# Sheet.net
KiCad netlist of a schematic drawn in Altium Designer
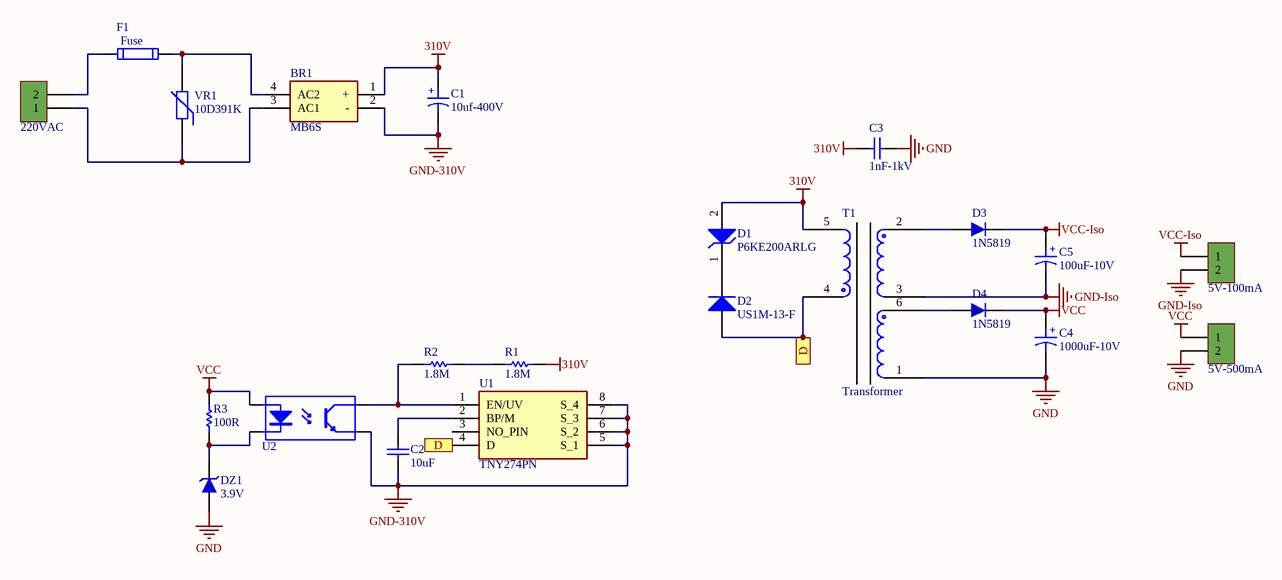
[diagram p0: Sheet.SchDoc]

(export (version "E")
  (design (tool "Eeschema 10.0.6"))
  (components
    (comp (ref "5V-100mA")
      (value "Phoenix 2 Pin")
      (footprint "Phoenix_2PIN_RA_P5.08mm")
      (libsource (lib "Connector") (part "Phoenix 2 Pin"))
    )
    (comp (ref "5V-500mA")
      (value "Phoenix 2 Pin")
      (footprint "Phoenix_2PIN_RA_P5.08mm")
      (libsource (lib "Connector") (part "Phoenix 2 Pin"))
    )
    (comp (ref "220VAC")
      (value "Phoenix 2 Pin")
      (footprint "Phoenix_2PIN_RA_P5.08mm")
      (libsource (lib "") (part "Phoenix 2 Pin_1"))
    )
    (comp (ref "BR1")
      (value "MB6S")
      (footprint "SamacSys:SOP250P700X270-4N")
      (description "Bridge Rectifier")
      (libsource (lib "*") (part "MB6S"))
    )
    (comp (ref "C1")
      (value "10uf-400V")
      (footprint "Cap electrolitic radial 10x16-5")
      (description "Cap electrolitic radial")
      (fields (field (name "DESIGNER") "Abbas Basereh"))
      (libsource (lib "Schematic") (part "Cap ELECTROLITIC TOTAL SIZE"))
    )
    (comp (ref "C2")
      (value "10uF")
      (footprint "CAP805")
      (description "TOTAL CAPACITOR SMD PACK")
      (fields (field (name "DESIGNER") "Abbas Basereh"))
      (libsource (lib "Altium") (part "CAP SMD PACKAGE"))
    )
    (comp (ref "C3")
      (value "1nF-1kV")
      (footprint "CAP1206")
      (description "TOTAL CAPACITOR SMD PACK")
      (fields (field (name "DESIGNER") "Abbas Basereh"))
      (libsource (lib "Altium") (part "CAP SMD PACKAGE"))
    )
    (comp (ref "C4")
      (value "1000uF-10V")
      (footprint "Cap electrolitic radial 8x12-3.5")
      (description "Cap electrolitic radial")
      (fields (field (name "DESIGNER") "Abbas Basereh"))
      (libsource (lib "Altium") (part "Cap ELECTROLITIC TOTAL SIZE"))
    )
    (comp (ref "C5")
      (value "100uF-10V")
      (footprint "Cap electrolitic radial 5x11-2")
      (description "Cap electrolitic radial")
      (fields (field (name "DESIGNER") "Abbas Basereh"))
      (libsource (lib "Altium") (part "Cap ELECTROLITIC TOTAL SIZE"))
    )
    (comp (ref "D1")
      (value "P6KE200ARLG")
      (footprint "ONSC-SURMETIC40-2-017AA-01")
      (description "600 W Peak Power Transient Voltage Suppressor, 2-Pin Surmetic(TM) 40, Pb-Free, Tape and Reel")
      (fields (field (name "MANUFACTURER") "On Semiconductor"))
      (libsource (lib "Altium Content Vault") (part "ONSC-K1A2-2"))
    )
    (comp (ref "D2")
      (value "US1M-13-F")
      (footprint "DIOD-SMA-2_A_V")
      (description "Ultra-Fast Rectifier, 1 A, 1.7 V, -65 to 150 degC, 2-Pin SMA, RoHS, Tape and Reel")
      (fields (field (name "MANUFACTURER") "Diodes Inc"))
      (libsource (lib "Altium Content Vault") (part "D-AK-2"))
    )
    (comp (ref "D3")
      (value "1N5819")
      (footprint "430X270D")
      (description "Schottkey Rectifiers")
      (fields (field (name "DESIGNER") "Abbas Basereh"))
      (libsource (lib "Altium") (part "1N5819"))
    )
    (comp (ref "D4")
      (value "1N5819")
      (footprint "430X270D")
      (description "Schottkey Rectifiers")
      (fields (field (name "DESIGNER") "Abbas Basereh"))
      (libsource (lib "Altium") (part "1N5819"))
    )
    (comp (ref "DZ1")
      (value "3.9V")
      (footprint "SOD80, LL-34")
      (description "DIODE ZENER GENERAL")
      (fields (field (name "PUBLISHER") "Abbas Basereh"))
      (libsource (lib "Altium") (part "ZENER GENERAL DIODE"))
    )
    (comp (ref "F1")
      (value "FUSE_HOLDER_METAL")
      (footprint "FUSE_5X20MM_4PIN")
      (libsource (lib "Fuse") (part "FUSE METAL 4PIN"))
    )
    (comp (ref "R1")
      (value "1.8M")
      (footprint "RES0603_(1608X06L)")
      (description "TOTAL SMD RESISTOR PACK")
      (fields (field (name "DESIGNER") "Abbas Basereh"))
      (libsource (lib "Altium") (part "RES SMD PACKAGE"))
    )
    (comp (ref "R2")
      (value "1.8M")
      (footprint "RES0603_(1608X06L)")
      (description "TOTAL SMD RESISTOR PACK")
      (fields (field (name "DESIGNER") "Abbas Basereh"))
      (libsource (lib "Altium") (part "RES SMD PACKAGE"))
    )
    (comp (ref "R3")
      (value "100R")
      (footprint "RES0603_(1608X06L)")
      (description "TOTAL SMD RESISTOR PACK")
      (fields (field (name "DESIGNER") "Abbas Basereh"))
      (libsource (lib "Altium") (part "RES SMD PACKAGE"))
    )
    (comp (ref "T1") (value "Transformer") (footprint "EE16") (libsource (lib "EE16") (part "EE16")))
    (comp (ref "U1")
      (value "TNY274PN")
      (footprint "SamacSys:DIP762W56P254L958H406Q8N")
      (description "Integrated Circuit")
      (fields (field (name "MOUSER PART NUMBER") "869-TNY274PN"))
      (libsource (lib "*") (part "TNY274PN"))
    )
    (comp (ref "U2")
      (value "PC817")
      (footprint "SOP4")
      (description "General Purpose Photocoupler")
      (libsource (lib "Peripheral") (part "PC817"))
    )
    (comp (ref "VR1")
      (value "10D391K")
      (footprint "10D XXX")
      (description "VARISTORS")
      (fields
        (field (name "MANUFACTURER") "china-canada-philipina")
        (field (name "DESIGNER") "Abbas Basereh")
        (field (name "PUBLISHER") "ABBAS BASEREH")
      )
      (libsource (lib "Schematic") (part "VARISTOR (VDR)"))
    )
  )
  (nets
    (net (code "1") (name "/D") (class "Default")
      (node (ref "D2") (pin "1") (pinfunction "A_1") (pintype "passive"))
      (node (ref "T1") (pin "4") (pinfunction "4_4") (pintype "passive"))
      (node (ref "U1") (pin "4") (pinfunction "D_4") (pintype "passive"))
    )
    (net (code "2") (name "310V") (class "Default")
      (node (ref "BR1") (pin "1") (pinfunction "+_1") (pintype "passive"))
      (node (ref "C1") (pin "1") (pinfunction "1_1") (pintype "passive"))
      (node (ref "C3") (pin "2") (pinfunction "2_2") (pintype "passive"))
      (node (ref "D1") (pin "2") (pinfunction "A_2") (pintype "passive"))
      (node (ref "R1") (pin "2") (pinfunction "2_2") (pintype "passive"))
      (node (ref "T1") (pin "5") (pinfunction "5_5") (pintype "passive"))
    )
    (net (code "3") (name "GND") (class "Default")
      (node (ref "5V-500mA") (pin "2") (pinfunction "2_2") (pintype "passive"))
      (node (ref "C3") (pin "1") (pinfunction "1_1") (pintype "passive"))
      (node (ref "C4") (pin "2") (pinfunction "2_2") (pintype "passive"))
      (node (ref "DZ1") (pin "1") (pintype "passive"))
      (node (ref "T1") (pin "1") (pinfunction "1_1") (pintype "passive"))
    )
    (net (code "4") (name "GND-310V") (class "Default")
      (node (ref "BR1") (pin "2") (pinfunction "-_2") (pintype "passive"))
      (node (ref "C1") (pin "2") (pinfunction "2_2") (pintype "passive"))
      (node (ref "C2") (pin "1") (pinfunction "1_1") (pintype "passive"))
      (node (ref "U1") (pin "5") (pinfunction "S_1_5") (pintype "passive"))
      (node (ref "U1") (pin "6") (pinfunction "S_2_6") (pintype "passive"))
      (node (ref "U1") (pin "7") (pinfunction "S_3_7") (pintype "passive"))
      (node (ref "U1") (pin "8") (pinfunction "S_4_8") (pintype "passive"))
      (node (ref "U2") (pin "3") (pinfunction "E_3") (pintype "passive"))
    )
    (net (code "5") (name "GND-Iso") (class "Default")
      (node (ref "5V-100mA") (pin "2") (pinfunction "2_2") (pintype "passive"))
      (node (ref "C5") (pin "2") (pinfunction "2_2") (pintype "passive"))
      (node (ref "T1") (pin "3") (pinfunction "3_3") (pintype "passive"))
    )
    (net (code "6") (name "Net-(220VAC-Pad2)") (class "Default")
      (node (ref "220VAC") (pin "2") (pinfunction "2_2") (pintype "passive"))
      (node (ref "F1") (pin "1") (pinfunction "1_1") (pintype "passive"))
    )
    (net (code "7") (name "Net-(BR1-AC1)") (class "Default")
      (node (ref "220VAC") (pin "1") (pinfunction "1_1") (pintype "passive"))
      (node (ref "BR1") (pin "3") (pinfunction "AC1_3") (pintype "passive"))
      (node (ref "VR1") (pin "1") (pinfunction "1_1") (pintype "passive"))
    )
    (net (code "8") (name "Net-(BR1-AC2)") (class "Default")
      (node (ref "BR1") (pin "4") (pinfunction "AC2_4") (pintype "passive"))
      (node (ref "F1") (pin "2") (pinfunction "2_2") (pintype "passive"))
      (node (ref "VR1") (pin "2") (pinfunction "2_2") (pintype "passive"))
    )
    (net (code "9") (name "Net-(D1-K)") (class "Default")
      (node (ref "D1") (pin "1") (pinfunction "K_1") (pintype "passive"))
      (node (ref "D2") (pin "2") (pinfunction "K_2") (pintype "passive"))
    )
    (net (code "10") (name "Net-(D3-Pad1)") (class "Default")
      (node (ref "D3") (pin "1") (pintype "passive"))
      (node (ref "T1") (pin "2") (pinfunction "2_2") (pintype "passive"))
    )
    (net (code "11") (name "Net-(D4-Pad1)") (class "Default")
      (node (ref "D4") (pin "1") (pintype "passive"))
      (node (ref "T1") (pin "6") (pinfunction "6_6") (pintype "passive"))
    )
    (net (code "12") (name "Net-(R1-Pad1)") (class "Default")
      (node (ref "R1") (pin "1") (pinfunction "1_1") (pintype "passive"))
      (node (ref "R2") (pin "2") (pinfunction "2_2") (pintype "passive"))
    )
    (net (code "13") (name "Net-(U1-BP{slash}M)") (class "Default")
      (node (ref "C2") (pin "2") (pinfunction "2_2") (pintype "passive"))
      (node (ref "U1") (pin "2") (pinfunction "BP/M_2") (pintype "passive"))
    )
    (net (code "14") (name "Net-(U1-EN{slash}UV)") (class "Default")
      (node (ref "R2") (pin "1") (pinfunction "1_1") (pintype "passive"))
      (node (ref "U1") (pin "1") (pinfunction "EN/UV_1") (pintype "passive"))
      (node (ref "U2") (pin "4") (pinfunction "C_4") (pintype "passive"))
    )
    (net (code "15") (name "Net-(U2-K)") (class "Default")
      (node (ref "DZ1") (pin "2") (pintype "passive"))
      (node (ref "R3") (pin "1") (pinfunction "1_1") (pintype "passive"))
      (node (ref "U2") (pin "2") (pinfunction "K_2") (pintype "passive"))
    )
    (net (code "16") (name "VCC") (class "Default")
      (node (ref "5V-500mA") (pin "1") (pinfunction "1_1") (pintype "passive"))
      (node (ref "C4") (pin "1") (pinfunction "1_1") (pintype "passive"))
      (node (ref "D4") (pin "2") (pintype "passive"))
      (node (ref "R3") (pin "2") (pinfunction "2_2") (pintype "passive"))
      (node (ref "U2") (pin "1") (pinfunction "A_1") (pintype "passive"))
    )
    (net (code "17") (name "VCC-Iso") (class "Default")
      (node (ref "5V-100mA") (pin "1") (pinfunction "1_1") (pintype "passive"))
      (node (ref "C5") (pin "1") (pinfunction "1_1") (pintype "passive"))
      (node (ref "D3") (pin "2") (pintype "passive"))
    )
    (net (code "18") (name "unconnected-(U1-NO_PIN-Pad3)") (class "Default")
      (node (ref "U1") (pin "3") (pinfunction "NO_PIN_3") (pintype "passive"))
    )
  )
)
